# BATT_DISP.net
KiCad netlist of a schematic drawn in EAGLE
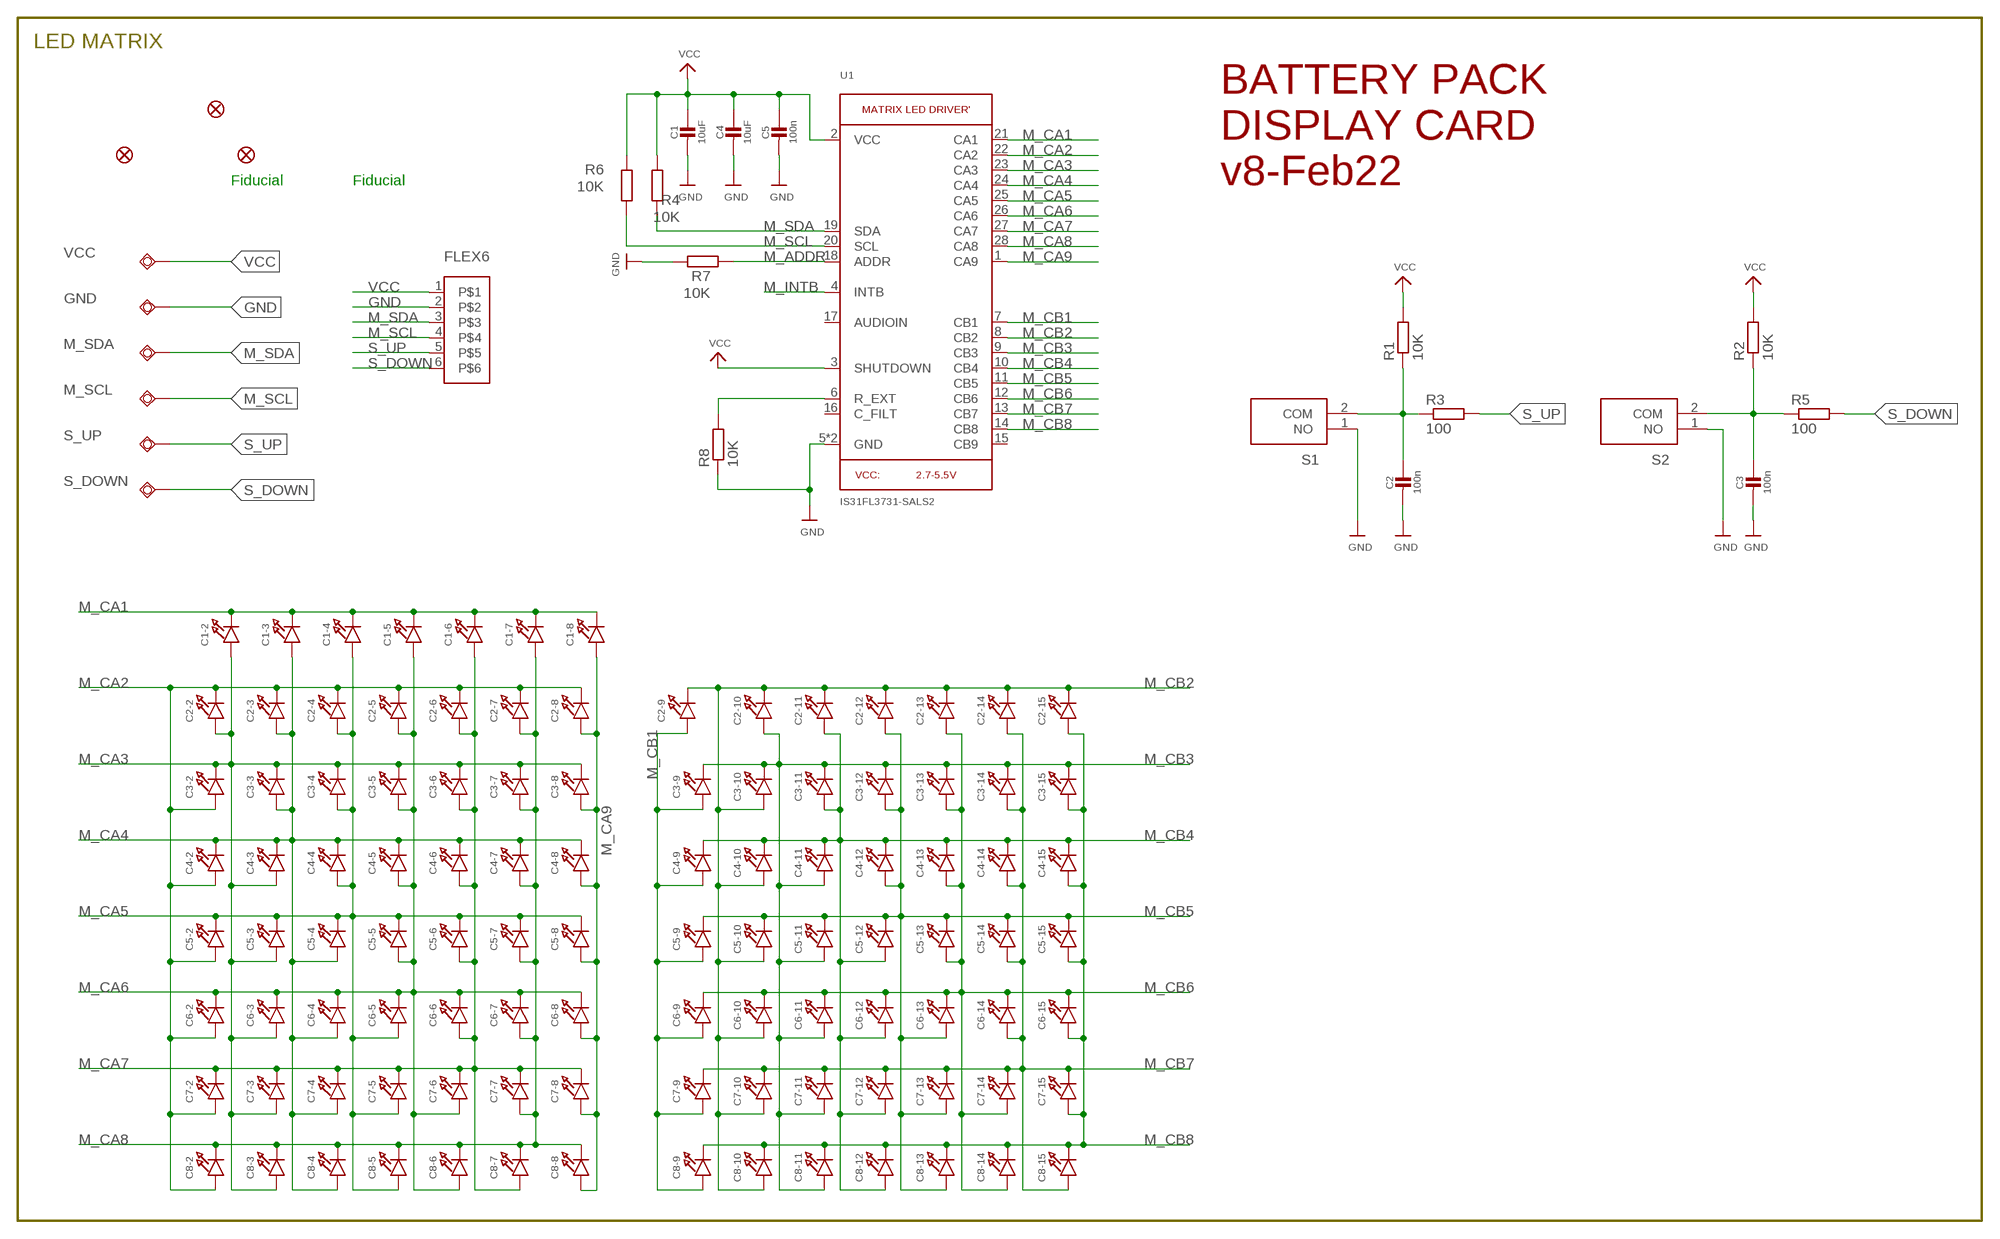
[diagram p0: schematic, sheet 1]

(export (version "E")
  (design (tool "Eeschema 10.0.6"))
  (components
    (comp (ref "C1")
      (value "10uF")
      (footprint "eagle-import:0805-NO")
      (libsource (lib "eagle-import") (part "CAP_CERAMIC0805-NOOUTLINE"))
    )
    (comp (ref "C1-2")
      (value "LED0402_NOOUTLINE")
      (footprint "eagle-import:CHIPLED_0402_NOOUTLINE")
      (libsource (lib "eagle-import") (part "LED0402_NOOUTLINE"))
    )
    (comp (ref "C1-3")
      (value "LED0402_NOOUTLINE")
      (footprint "eagle-import:CHIPLED_0402_NOOUTLINE")
      (libsource (lib "eagle-import") (part "LED0402_NOOUTLINE"))
    )
    (comp (ref "C1-4")
      (value "LED0402_NOOUTLINE")
      (footprint "eagle-import:CHIPLED_0402_NOOUTLINE")
      (libsource (lib "eagle-import") (part "LED0402_NOOUTLINE"))
    )
    (comp (ref "C1-5")
      (value "LED0402_NOOUTLINE")
      (footprint "eagle-import:CHIPLED_0402_NOOUTLINE")
      (libsource (lib "eagle-import") (part "LED0402_NOOUTLINE"))
    )
    (comp (ref "C1-6")
      (value "LED0402_NOOUTLINE")
      (footprint "eagle-import:CHIPLED_0402_NOOUTLINE")
      (libsource (lib "eagle-import") (part "LED0402_NOOUTLINE"))
    )
    (comp (ref "C1-7")
      (value "LED0402_NOOUTLINE")
      (footprint "eagle-import:CHIPLED_0402_NOOUTLINE")
      (libsource (lib "eagle-import") (part "LED0402_NOOUTLINE"))
    )
    (comp (ref "C1-8")
      (value "LED0402_NOOUTLINE")
      (footprint "eagle-import:CHIPLED_0402_NOOUTLINE")
      (libsource (lib "eagle-import") (part "LED0402_NOOUTLINE"))
    )
    (comp (ref "C2")
      (value "100n")
      (footprint "eagle-import:0805-NO")
      (libsource (lib "eagle-import") (part "CAP_CERAMIC0805-NOOUTLINE"))
    )
    (comp (ref "C2-2")
      (value "LED0402_NOOUTLINE")
      (footprint "eagle-import:CHIPLED_0402_NOOUTLINE")
      (libsource (lib "eagle-import") (part "LED0402_NOOUTLINE"))
    )
    (comp (ref "C2-3")
      (value "LED0402_NOOUTLINE")
      (footprint "eagle-import:CHIPLED_0402_NOOUTLINE")
      (libsource (lib "eagle-import") (part "LED0402_NOOUTLINE"))
    )
    (comp (ref "C2-4")
      (value "LED0402_NOOUTLINE")
      (footprint "eagle-import:CHIPLED_0402_NOOUTLINE")
      (libsource (lib "eagle-import") (part "LED0402_NOOUTLINE"))
    )
    (comp (ref "C2-5")
      (value "LED0402_NOOUTLINE")
      (footprint "eagle-import:CHIPLED_0402_NOOUTLINE")
      (libsource (lib "eagle-import") (part "LED0402_NOOUTLINE"))
    )
    (comp (ref "C2-6")
      (value "LED0402_NOOUTLINE")
      (footprint "eagle-import:CHIPLED_0402_NOOUTLINE")
      (libsource (lib "eagle-import") (part "LED0402_NOOUTLINE"))
    )
    (comp (ref "C2-7")
      (value "LED0402_NOOUTLINE")
      (footprint "eagle-import:CHIPLED_0402_NOOUTLINE")
      (libsource (lib "eagle-import") (part "LED0402_NOOUTLINE"))
    )
    (comp (ref "C2-8")
      (value "LED0402_NOOUTLINE")
      (footprint "eagle-import:CHIPLED_0402_NOOUTLINE")
      (libsource (lib "eagle-import") (part "LED0402_NOOUTLINE"))
    )
    (comp (ref "C2-9")
      (value "LED0402_NOOUTLINE")
      (footprint "eagle-import:CHIPLED_0402_NOOUTLINE")
      (libsource (lib "eagle-import") (part "LED0402_NOOUTLINE"))
    )
    (comp (ref "C2-10")
      (value "LED0402_NOOUTLINE")
      (footprint "eagle-import:CHIPLED_0402_NOOUTLINE")
      (libsource (lib "eagle-import") (part "LED0402_NOOUTLINE"))
    )
    (comp (ref "C2-11")
      (value "LED0402_NOOUTLINE")
      (footprint "eagle-import:CHIPLED_0402_NOOUTLINE")
      (libsource (lib "eagle-import") (part "LED0402_NOOUTLINE"))
    )
    (comp (ref "C2-12")
      (value "LED0402_NOOUTLINE")
      (footprint "eagle-import:CHIPLED_0402_NOOUTLINE")
      (libsource (lib "eagle-import") (part "LED0402_NOOUTLINE"))
    )
    (comp (ref "C2-13")
      (value "LED0402_NOOUTLINE")
      (footprint "eagle-import:CHIPLED_0402_NOOUTLINE")
      (libsource (lib "eagle-import") (part "LED0402_NOOUTLINE"))
    )
    (comp (ref "C2-14")
      (value "LED0402_NOOUTLINE")
      (footprint "eagle-import:CHIPLED_0402_NOOUTLINE")
      (libsource (lib "eagle-import") (part "LED0402_NOOUTLINE"))
    )
    (comp (ref "C2-15")
      (value "LED0402_NOOUTLINE")
      (footprint "eagle-import:CHIPLED_0402_NOOUTLINE")
      (libsource (lib "eagle-import") (part "LED0402_NOOUTLINE"))
    )
    (comp (ref "C3")
      (value "100n")
      (footprint "eagle-import:0805-NO")
      (libsource (lib "eagle-import") (part "CAP_CERAMIC0805-NOOUTLINE"))
    )
    (comp (ref "C3-2")
      (value "LED0402_NOOUTLINE")
      (footprint "eagle-import:CHIPLED_0402_NOOUTLINE")
      (libsource (lib "eagle-import") (part "LED0402_NOOUTLINE"))
    )
    (comp (ref "C3-3")
      (value "LED0402_NOOUTLINE")
      (footprint "eagle-import:CHIPLED_0402_NOOUTLINE")
      (libsource (lib "eagle-import") (part "LED0402_NOOUTLINE"))
    )
    (comp (ref "C3-4")
      (value "LED0402_NOOUTLINE")
      (footprint "eagle-import:CHIPLED_0402_NOOUTLINE")
      (libsource (lib "eagle-import") (part "LED0402_NOOUTLINE"))
    )
    (comp (ref "C3-5")
      (value "LED0402_NOOUTLINE")
      (footprint "eagle-import:CHIPLED_0402_NOOUTLINE")
      (libsource (lib "eagle-import") (part "LED0402_NOOUTLINE"))
    )
    (comp (ref "C3-6")
      (value "LED0402_NOOUTLINE")
      (footprint "eagle-import:CHIPLED_0402_NOOUTLINE")
      (libsource (lib "eagle-import") (part "LED0402_NOOUTLINE"))
    )
    (comp (ref "C3-7")
      (value "LED0402_NOOUTLINE")
      (footprint "eagle-import:CHIPLED_0402_NOOUTLINE")
      (libsource (lib "eagle-import") (part "LED0402_NOOUTLINE"))
    )
    (comp (ref "C3-8")
      (value "LED0402_NOOUTLINE")
      (footprint "eagle-import:CHIPLED_0402_NOOUTLINE")
      (libsource (lib "eagle-import") (part "LED0402_NOOUTLINE"))
    )
    (comp (ref "C3-9")
      (value "LED0402_NOOUTLINE")
      (footprint "eagle-import:CHIPLED_0402_NOOUTLINE")
      (libsource (lib "eagle-import") (part "LED0402_NOOUTLINE"))
    )
    (comp (ref "C3-10")
      (value "LED0402_NOOUTLINE")
      (footprint "eagle-import:CHIPLED_0402_NOOUTLINE")
      (libsource (lib "eagle-import") (part "LED0402_NOOUTLINE"))
    )
    (comp (ref "C3-11")
      (value "LED0402_NOOUTLINE")
      (footprint "eagle-import:CHIPLED_0402_NOOUTLINE")
      (libsource (lib "eagle-import") (part "LED0402_NOOUTLINE"))
    )
    (comp (ref "C3-12")
      (value "LED0402_NOOUTLINE")
      (footprint "eagle-import:CHIPLED_0402_NOOUTLINE")
      (libsource (lib "eagle-import") (part "LED0402_NOOUTLINE"))
    )
    (comp (ref "C3-13")
      (value "LED0402_NOOUTLINE")
      (footprint "eagle-import:CHIPLED_0402_NOOUTLINE")
      (libsource (lib "eagle-import") (part "LED0402_NOOUTLINE"))
    )
    (comp (ref "C3-14")
      (value "LED0402_NOOUTLINE")
      (footprint "eagle-import:CHIPLED_0402_NOOUTLINE")
      (libsource (lib "eagle-import") (part "LED0402_NOOUTLINE"))
    )
    (comp (ref "C3-15")
      (value "LED0402_NOOUTLINE")
      (footprint "eagle-import:CHIPLED_0402_NOOUTLINE")
      (libsource (lib "eagle-import") (part "LED0402_NOOUTLINE"))
    )
    (comp (ref "C4")
      (value "10uF")
      (footprint "eagle-import:0805-NO")
      (libsource (lib "eagle-import") (part "CAP_CERAMIC0805-NOOUTLINE"))
    )
    (comp (ref "C4-2")
      (value "LED0402_NOOUTLINE")
      (footprint "eagle-import:CHIPLED_0402_NOOUTLINE")
      (libsource (lib "eagle-import") (part "LED0402_NOOUTLINE"))
    )
    (comp (ref "C4-3")
      (value "LED0402_NOOUTLINE")
      (footprint "eagle-import:CHIPLED_0402_NOOUTLINE")
      (libsource (lib "eagle-import") (part "LED0402_NOOUTLINE"))
    )
    (comp (ref "C4-4")
      (value "LED0402_NOOUTLINE")
      (footprint "eagle-import:CHIPLED_0402_NOOUTLINE")
      (libsource (lib "eagle-import") (part "LED0402_NOOUTLINE"))
    )
    (comp (ref "C4-5")
      (value "LED0402_NOOUTLINE")
      (footprint "eagle-import:CHIPLED_0402_NOOUTLINE")
      (libsource (lib "eagle-import") (part "LED0402_NOOUTLINE"))
    )
    (comp (ref "C4-6")
      (value "LED0402_NOOUTLINE")
      (footprint "eagle-import:CHIPLED_0402_NOOUTLINE")
      (libsource (lib "eagle-import") (part "LED0402_NOOUTLINE"))
    )
    (comp (ref "C4-7")
      (value "LED0402_NOOUTLINE")
      (footprint "eagle-import:CHIPLED_0402_NOOUTLINE")
      (libsource (lib "eagle-import") (part "LED0402_NOOUTLINE"))
    )
    (comp (ref "C4-8")
      (value "LED0402_NOOUTLINE")
      (footprint "eagle-import:CHIPLED_0402_NOOUTLINE")
      (libsource (lib "eagle-import") (part "LED0402_NOOUTLINE"))
    )
    (comp (ref "C4-9")
      (value "LED0402_NOOUTLINE")
      (footprint "eagle-import:CHIPLED_0402_NOOUTLINE")
      (libsource (lib "eagle-import") (part "LED0402_NOOUTLINE"))
    )
    (comp (ref "C4-10")
      (value "LED0402_NOOUTLINE")
      (footprint "eagle-import:CHIPLED_0402_NOOUTLINE")
      (libsource (lib "eagle-import") (part "LED0402_NOOUTLINE"))
    )
    (comp (ref "C4-11")
      (value "LED0402_NOOUTLINE")
      (footprint "eagle-import:CHIPLED_0402_NOOUTLINE")
      (libsource (lib "eagle-import") (part "LED0402_NOOUTLINE"))
    )
    (comp (ref "C4-12")
      (value "LED0402_NOOUTLINE")
      (footprint "eagle-import:CHIPLED_0402_NOOUTLINE")
      (libsource (lib "eagle-import") (part "LED0402_NOOUTLINE"))
    )
    (comp (ref "C4-13")
      (value "LED0402_NOOUTLINE")
      (footprint "eagle-import:CHIPLED_0402_NOOUTLINE")
      (libsource (lib "eagle-import") (part "LED0402_NOOUTLINE"))
    )
    (comp (ref "C4-14")
      (value "LED0402_NOOUTLINE")
      (footprint "eagle-import:CHIPLED_0402_NOOUTLINE")
      (libsource (lib "eagle-import") (part "LED0402_NOOUTLINE"))
    )
    (comp (ref "C4-15")
      (value "LED0402_NOOUTLINE")
      (footprint "eagle-import:CHIPLED_0402_NOOUTLINE")
      (libsource (lib "eagle-import") (part "LED0402_NOOUTLINE"))
    )
    (comp (ref "C5")
      (value "100n")
      (footprint "eagle-import:0805-NO")
      (libsource (lib "eagle-import") (part "CAP_CERAMIC0805-NOOUTLINE"))
    )
    (comp (ref "C5-2")
      (value "LED0402_NOOUTLINE")
      (footprint "eagle-import:CHIPLED_0402_NOOUTLINE")
      (libsource (lib "eagle-import") (part "LED0402_NOOUTLINE"))
    )
    (comp (ref "C5-3")
      (value "LED0402_NOOUTLINE")
      (footprint "eagle-import:CHIPLED_0402_NOOUTLINE")
      (libsource (lib "eagle-import") (part "LED0402_NOOUTLINE"))
    )
    (comp (ref "C5-4")
      (value "LED0402_NOOUTLINE")
      (footprint "eagle-import:CHIPLED_0402_NOOUTLINE")
      (libsource (lib "eagle-import") (part "LED0402_NOOUTLINE"))
    )
    (comp (ref "C5-5")
      (value "LED0402_NOOUTLINE")
      (footprint "eagle-import:CHIPLED_0402_NOOUTLINE")
      (libsource (lib "eagle-import") (part "LED0402_NOOUTLINE"))
    )
    (comp (ref "C5-6")
      (value "LED0402_NOOUTLINE")
      (footprint "eagle-import:CHIPLED_0402_NOOUTLINE")
      (libsource (lib "eagle-import") (part "LED0402_NOOUTLINE"))
    )
    (comp (ref "C5-7")
      (value "LED0402_NOOUTLINE")
      (footprint "eagle-import:CHIPLED_0402_NOOUTLINE")
      (libsource (lib "eagle-import") (part "LED0402_NOOUTLINE"))
    )
    (comp (ref "C5-8")
      (value "LED0402_NOOUTLINE")
      (footprint "eagle-import:CHIPLED_0402_NOOUTLINE")
      (libsource (lib "eagle-import") (part "LED0402_NOOUTLINE"))
    )
    (comp (ref "C5-9")
      (value "LED0402_NOOUTLINE")
      (footprint "eagle-import:CHIPLED_0402_NOOUTLINE")
      (libsource (lib "eagle-import") (part "LED0402_NOOUTLINE"))
    )
    (comp (ref "C5-10")
      (value "LED0402_NOOUTLINE")
      (footprint "eagle-import:CHIPLED_0402_NOOUTLINE")
      (libsource (lib "eagle-import") (part "LED0402_NOOUTLINE"))
    )
    (comp (ref "C5-11")
      (value "LED0402_NOOUTLINE")
      (footprint "eagle-import:CHIPLED_0402_NOOUTLINE")
      (libsource (lib "eagle-import") (part "LED0402_NOOUTLINE"))
    )
    (comp (ref "C5-12")
      (value "LED0402_NOOUTLINE")
      (footprint "eagle-import:CHIPLED_0402_NOOUTLINE")
      (libsource (lib "eagle-import") (part "LED0402_NOOUTLINE"))
    )
    (comp (ref "C5-13")
      (value "LED0402_NOOUTLINE")
      (footprint "eagle-import:CHIPLED_0402_NOOUTLINE")
      (libsource (lib "eagle-import") (part "LED0402_NOOUTLINE"))
    )
    (comp (ref "C5-14")
      (value "LED0402_NOOUTLINE")
      (footprint "eagle-import:CHIPLED_0402_NOOUTLINE")
      (libsource (lib "eagle-import") (part "LED0402_NOOUTLINE"))
    )
    (comp (ref "C5-15")
      (value "LED0402_NOOUTLINE")
      (footprint "eagle-import:CHIPLED_0402_NOOUTLINE")
      (libsource (lib "eagle-import") (part "LED0402_NOOUTLINE"))
    )
    (comp (ref "C6-2")
      (value "LED0402_NOOUTLINE")
      (footprint "eagle-import:CHIPLED_0402_NOOUTLINE")
      (libsource (lib "eagle-import") (part "LED0402_NOOUTLINE"))
    )
    (comp (ref "C6-3")
      (value "LED0402_NOOUTLINE")
      (footprint "eagle-import:CHIPLED_0402_NOOUTLINE")
      (libsource (lib "eagle-import") (part "LED0402_NOOUTLINE"))
    )
    (comp (ref "C6-4")
      (value "LED0402_NOOUTLINE")
      (footprint "eagle-import:CHIPLED_0402_NOOUTLINE")
      (libsource (lib "eagle-import") (part "LED0402_NOOUTLINE"))
    )
    (comp (ref "C6-5")
      (value "LED0402_NOOUTLINE")
      (footprint "eagle-import:CHIPLED_0402_NOOUTLINE")
      (libsource (lib "eagle-import") (part "LED0402_NOOUTLINE"))
    )
    (comp (ref "C6-6")
      (value "LED0402_NOOUTLINE")
      (footprint "eagle-import:CHIPLED_0402_NOOUTLINE")
      (libsource (lib "eagle-import") (part "LED0402_NOOUTLINE"))
    )
    (comp (ref "C6-7")
      (value "LED0402_NOOUTLINE")
      (footprint "eagle-import:CHIPLED_0402_NOOUTLINE")
      (libsource (lib "eagle-import") (part "LED0402_NOOUTLINE"))
    )
    (comp (ref "C6-8")
      (value "LED0402_NOOUTLINE")
      (footprint "eagle-import:CHIPLED_0402_NOOUTLINE")
      (libsource (lib "eagle-import") (part "LED0402_NOOUTLINE"))
    )
    (comp (ref "C6-9")
      (value "LED0402_NOOUTLINE")
      (footprint "eagle-import:CHIPLED_0402_NOOUTLINE")
      (libsource (lib "eagle-import") (part "LED0402_NOOUTLINE"))
    )
    (comp (ref "C6-10")
      (value "LED0402_NOOUTLINE")
      (footprint "eagle-import:CHIPLED_0402_NOOUTLINE")
      (libsource (lib "eagle-import") (part "LED0402_NOOUTLINE"))
    )
    (comp (ref "C6-11")
      (value "LED0402_NOOUTLINE")
      (footprint "eagle-import:CHIPLED_0402_NOOUTLINE")
      (libsource (lib "eagle-import") (part "LED0402_NOOUTLINE"))
    )
    (comp (ref "C6-12")
      (value "LED0402_NOOUTLINE")
      (footprint "eagle-import:CHIPLED_0402_NOOUTLINE")
      (libsource (lib "eagle-import") (part "LED0402_NOOUTLINE"))
    )
    (comp (ref "C6-13")
      (value "LED0402_NOOUTLINE")
      (footprint "eagle-import:CHIPLED_0402_NOOUTLINE")
      (libsource (lib "eagle-import") (part "LED0402_NOOUTLINE"))
    )
    (comp (ref "C6-14")
      (value "LED0402_NOOUTLINE")
      (footprint "eagle-import:CHIPLED_0402_NOOUTLINE")
      (libsource (lib "eagle-import") (part "LED0402_NOOUTLINE"))
    )
    (comp (ref "C6-15")
      (value "LED0402_NOOUTLINE")
      (footprint "eagle-import:CHIPLED_0402_NOOUTLINE")
      (libsource (lib "eagle-import") (part "LED0402_NOOUTLINE"))
    )
    (comp (ref "C7-2")
      (value "LED0402_NOOUTLINE")
      (footprint "eagle-import:CHIPLED_0402_NOOUTLINE")
      (libsource (lib "eagle-import") (part "LED0402_NOOUTLINE"))
    )
    (comp (ref "C7-3")
      (value "LED0402_NOOUTLINE")
      (footprint "eagle-import:CHIPLED_0402_NOOUTLINE")
      (libsource (lib "eagle-import") (part "LED0402_NOOUTLINE"))
    )
    (comp (ref "C7-4")
      (value "LED0402_NOOUTLINE")
      (footprint "eagle-import:CHIPLED_0402_NOOUTLINE")
      (libsource (lib "eagle-import") (part "LED0402_NOOUTLINE"))
    )
    (comp (ref "C7-5")
      (value "LED0402_NOOUTLINE")
      (footprint "eagle-import:CHIPLED_0402_NOOUTLINE")
      (libsource (lib "eagle-import") (part "LED0402_NOOUTLINE"))
    )
    (comp (ref "C7-6")
      (value "LED0402_NOOUTLINE")
      (footprint "eagle-import:CHIPLED_0402_NOOUTLINE")
      (libsource (lib "eagle-import") (part "LED0402_NOOUTLINE"))
    )
    (comp (ref "C7-7")
      (value "LED0402_NOOUTLINE")
      (footprint "eagle-import:CHIPLED_0402_NOOUTLINE")
      (libsource (lib "eagle-import") (part "LED0402_NOOUTLINE"))
    )
    (comp (ref "C7-8")
      (value "LED0402_NOOUTLINE")
      (footprint "eagle-import:CHIPLED_0402_NOOUTLINE")
      (libsource (lib "eagle-import") (part "LED0402_NOOUTLINE"))
    )
    (comp (ref "C7-9")
      (value "LED0402_NOOUTLINE")
      (footprint "eagle-import:CHIPLED_0402_NOOUTLINE")
      (libsource (lib "eagle-import") (part "LED0402_NOOUTLINE"))
    )
    (comp (ref "C7-10")
      (value "LED0402_NOOUTLINE")
      (footprint "eagle-import:CHIPLED_0402_NOOUTLINE")
      (libsource (lib "eagle-import") (part "LED0402_NOOUTLINE"))
    )
    (comp (ref "C7-11")
      (value "LED0402_NOOUTLINE")
      (footprint "eagle-import:CHIPLED_0402_NOOUTLINE")
      (libsource (lib "eagle-import") (part "LED0402_NOOUTLINE"))
    )
    (comp (ref "C7-12")
      (value "LED0402_NOOUTLINE")
      (footprint "eagle-import:CHIPLED_0402_NOOUTLINE")
      (libsource (lib "eagle-import") (part "LED0402_NOOUTLINE"))
    )
    (comp (ref "C7-13")
      (value "LED0402_NOOUTLINE")
      (footprint "eagle-import:CHIPLED_0402_NOOUTLINE")
      (libsource (lib "eagle-import") (part "LED0402_NOOUTLINE"))
    )
    (comp (ref "C7-14")
      (value "LED0402_NOOUTLINE")
      (footprint "eagle-import:CHIPLED_0402_NOOUTLINE")
      (libsource (lib "eagle-import") (part "LED0402_NOOUTLINE"))
    )
    (comp (ref "C7-15")
      (value "LED0402_NOOUTLINE")
      (footprint "eagle-import:CHIPLED_0402_NOOUTLINE")
      (libsource (lib "eagle-import") (part "LED0402_NOOUTLINE"))
    )
    (comp (ref "C8-2")
      (value "LED0402_NOOUTLINE")
      (footprint "eagle-import:CHIPLED_0402_NOOUTLINE")
      (libsource (lib "eagle-import") (part "LED0402_NOOUTLINE"))
    )
    (comp (ref "C8-3")
      (value "LED0402_NOOUTLINE")
      (footprint "eagle-import:CHIPLED_0402_NOOUTLINE")
      (libsource (lib "eagle-import") (part "LED0402_NOOUTLINE"))
    )
    (comp (ref "C8-4")
      (value "LED0402_NOOUTLINE")
      (footprint "eagle-import:CHIPLED_0402_NOOUTLINE")
      (libsource (lib "eagle-import") (part "LED0402_NOOUTLINE"))
    )
    (comp (ref "C8-5")
      (value "LED0402_NOOUTLINE")
      (footprint "eagle-import:CHIPLED_0402_NOOUTLINE")
      (libsource (lib "eagle-import") (part "LED0402_NOOUTLINE"))
    )
    (comp (ref "C8-6")
      (value "LED0402_NOOUTLINE")
      (footprint "eagle-import:CHIPLED_0402_NOOUTLINE")
      (libsource (lib "eagle-import") (part "LED0402_NOOUTLINE"))
    )
    (comp (ref "C8-7")
      (value "LED0402_NOOUTLINE")
      (footprint "eagle-import:CHIPLED_0402_NOOUTLINE")
      (libsource (lib "eagle-import") (part "LED0402_NOOUTLINE"))
    )
    (comp (ref "C8-8")
      (value "LED0402_NOOUTLINE")
      (footprint "eagle-import:CHIPLED_0402_NOOUTLINE")
      (libsource (lib "eagle-import") (part "LED0402_NOOUTLINE"))
    )
    (comp (ref "C8-9")
      (value "LED0402_NOOUTLINE")
      (footprint "eagle-import:CHIPLED_0402_NOOUTLINE")
      (libsource (lib "eagle-import") (part "LED0402_NOOUTLINE"))
    )
    (comp (ref "C8-10")
      (value "LED0402_NOOUTLINE")
      (footprint "eagle-import:CHIPLED_0402_NOOUTLINE")
      (libsource (lib "eagle-import") (part "LED0402_NOOUTLINE"))
    )
    (comp (ref "C8-11")
      (value "LED0402_NOOUTLINE")
      (footprint "eagle-import:CHIPLED_0402_NOOUTLINE")
      (libsource (lib "eagle-import") (part "LED0402_NOOUTLINE"))
    )
    (comp (ref "C8-12")
      (value "LED0402_NOOUTLINE")
      (footprint "eagle-import:CHIPLED_0402_NOOUTLINE")
      (libsource (lib "eagle-import") (part "LED0402_NOOUTLINE"))
    )
    (comp (ref "C8-13")
      (value "LED0402_NOOUTLINE")
      (footprint "eagle-import:CHIPLED_0402_NOOUTLINE")
      (libsource (lib "eagle-import") (part "LED0402_NOOUTLINE"))
    )
    (comp (ref "C8-14")
      (value "LED0402_NOOUTLINE")
      (footprint "eagle-import:CHIPLED_0402_NOOUTLINE")
      (libsource (lib "eagle-import") (part "LED0402_NOOUTLINE"))
    )
    (comp (ref "C8-15")
      (value "LED0402_NOOUTLINE")
      (footprint "eagle-import:CHIPLED_0402_NOOUTLINE")
      (libsource (lib "eagle-import") (part "LED0402_NOOUTLINE"))
    )
    (comp (ref "FD1")
      (value "FIDUCIALUFIDUCIAL")
      (footprint "eagle-import:FIDUCIAL-MICRO")
      (libsource (lib "eagle-import") (part "FIDUCIALUFIDUCIAL"))
    )
    (comp (ref "FD2")
      (value "FIDUCIAL\"\"")
      (footprint "eagle-import:FIDUCIAL_1MM")
      (libsource (lib "eagle-import") (part "FIDUCIAL{dblquote}{dblquote}"))
    )
    (comp (ref "FD3")
      (value "FIDUCIAL\"\"")
      (footprint "eagle-import:FIDUCIAL_1MM")
      (libsource (lib "eagle-import") (part "FIDUCIAL{dblquote}{dblquote}"))
    )
    (comp (ref "GND")
      (value "TESTPAD_TPSQB1,27")
      (footprint "eagle-import:TESTPAD_B1,27")
      (libsource (lib "eagle-import") (part "TESTPAD_TPSQB1,27"))
    )
    (comp (ref "K1")
      (value "FLEX6")
      (footprint "eagle-import:FLEX6")
      (libsource (lib "eagle-import") (part "FLEX6"))
    )
    (comp (ref "M_SCL")
      (value "TESTPAD_TPSQB1,27")
      (footprint "eagle-import:TESTPAD_B1,27")
      (libsource (lib "eagle-import") (part "TESTPAD_TPSQB1,27"))
    )
    (comp (ref "M_SDA")
      (value "TESTPAD_TPSQB1,27")
      (footprint "eagle-import:TESTPAD_B1,27")
      (libsource (lib "eagle-import") (part "TESTPAD_TPSQB1,27"))
    )
    (comp (ref "R1")
      (value "10K")
      (footprint "eagle-import:R0603")
      (libsource (lib "eagle-import") (part "R-EU_R0603"))
    )
    (comp (ref "R2")
      (value "10K")
      (footprint "eagle-import:R0603")
      (libsource (lib "eagle-import") (part "R-EU_R0603"))
    )
    (comp (ref "R3")
      (value "100")
      (footprint "eagle-import:R0603")
      (libsource (lib "eagle-import") (part "R-EU_R0603"))
    )
    (comp (ref "R4")
      (value "10K")
      (footprint "eagle-import:R0603")
      (libsource (lib "eagle-import") (part "R-EU_R0603"))
    )
    (comp (ref "R5")
      (value "100")
      (footprint "eagle-import:R0603")
      (libsource (lib "eagle-import") (part "R-EU_R0603"))
    )
    (comp (ref "R6")
      (value "10K")
      (footprint "eagle-import:R0603")
      (libsource (lib "eagle-import") (part "R-EU_R0603"))
    )
    (comp (ref "R7")
      (value "10K")
      (footprint "eagle-import:R0603")
      (libsource (lib "eagle-import") (part "R-EU_R0603"))
    )
    (comp (ref "R8")
      (value "10K")
      (footprint "eagle-import:R0603")
      (libsource (lib "eagle-import") (part "R-EU_R0603"))
    )
    (comp (ref "S1")
      (value "KXT311LHS")
      (footprint "eagle-import:KXT311LHS")
      (fields (field (name "MOUSER_PART_NUMBER") "611-KXT311LHS"))
      (libsource (lib "eagle-import") (part "KXT311LHS"))
    )
    (comp (ref "S2")
      (value "KXT311LHS")
      (footprint "eagle-import:KXT311LHS")
      (fields (field (name "MOUSER_PART_NUMBER") "611-KXT311LHS"))
      (libsource (lib "eagle-import") (part "KXT311LHS"))
    )
    (comp (ref "S_DOWN")
      (value "TESTPAD_TPSQB1,27")
      (footprint "eagle-import:TESTPAD_B1,27")
      (libsource (lib "eagle-import") (part "TESTPAD_TPSQB1,27"))
    )
    (comp (ref "S_UP")
      (value "TESTPAD_TPSQB1,27")
      (footprint "eagle-import:TESTPAD_B1,27")
      (libsource (lib "eagle-import") (part "TESTPAD_TPSQB1,27"))
    )
    (comp (ref "U1")
      (value "IS31FL3731-SALS2")
      (footprint "eagle-import:QFN28_4MM_0.4MM")
      (libsource (lib "eagle-import") (part "IS31FL3731QFN"))
    )
    (comp (ref "VCC")
      (value "TESTPAD_TPSQB1,27")
      (footprint "eagle-import:TESTPAD_B1,27")
      (libsource (lib "eagle-import") (part "TESTPAD_TPSQB1,27"))
    )
  )
  (nets
    (net (code "1") (name "/M_ADDR") (class "Default")
      (node (ref "R7") (pin "1") (pinfunction "1_1") (pintype "passive"))
      (node (ref "U1") (pin "18") (pinfunction "ADDR_18") (pintype "bidirectional"))
    )
    (net (code "2") (name "/M_CA1") (class "Default")
      (node (ref "C1-2") (pin "C") (pinfunction "C_C") (pintype "passive"))
      (node (ref "C1-3") (pin "C") (pinfunction "C_C") (pintype "passive"))
      (node (ref "C1-4") (pin "C") (pinfunction "C_C") (pintype "passive"))
      (node (ref "C1-5") (pin "C") (pinfunction "C_C") (pintype "passive"))
      (node (ref "C1-6") (pin "C") (pinfunction "C_C") (pintype "passive"))
      (node (ref "C1-7") (pin "C") (pinfunction "C_C") (pintype "passive"))
      (node (ref "C1-8") (pin "C") (pinfunction "C_C") (pintype "passive"))
      (node (ref "U1") (pin "21") (pinfunction "CA1_21") (pintype "bidirectional"))
    )
    (net (code "3") (name "/M_CA2") (class "Default")
      (node (ref "C2-2") (pin "C") (pinfunction "C_C") (pintype "passive"))
      (node (ref "C2-3") (pin "C") (pinfunction "C_C") (pintype "passive"))
      (node (ref "C2-4") (pin "C") (pinfunction "C_C") (pintype "passive"))
      (node (ref "C2-5") (pin "C") (pinfunction "C_C") (pintype "passive"))
      (node (ref "C2-6") (pin "C") (pinfunction "C_C") (pintype "passive"))
      (node (ref "C2-7") (pin "C") (pinfunction "C_C") (pintype "passive"))
      (node (ref "C2-8") (pin "C") (pinfunction "C_C") (pintype "passive"))
      (node (ref "C3-2") (pin "A") (pinfunction "A_A") (pintype "passive"))
      (node (ref "C4-2") (pin "A") (pinfunction "A_A") (pintype "passive"))
      (node (ref "C5-2") (pin "A") (pinfunction "A_A") (pintype "passive"))
      (node (ref "C6-2") (pin "A") (pinfunction "A_A") (pintype "passive"))
      (node (ref "C7-2") (pin "A") (pinfunction "A_A") (pintype "passive"))
      (node (ref "C8-2") (pin "A") (pinfunction "A_A") (pintype "passive"))
      (node (ref "U1") (pin "22") (pinfunction "CA2_22") (pintype "bidirectional"))
    )
    (net (code "4") (name "/M_CA3") (class "Default")
      (node (ref "C1-2") (pin "A") (pinfunction "A_A") (pintype "passive"))
      (node (ref "C2-2") (pin "A") (pinfunction "A_A") (pintype "passive"))
      (node (ref "C3-2") (pin "C") (pinfunction "C_C") (pintype "passive"))
      (node (ref "C3-3") (pin "C") (pinfunction "C_C") (pintype "passive"))
      (node (ref "C3-4") (pin "C") (pinfunction "C_C") (pintype "passive"))
      (node (ref "C3-5") (pin "C") (pinfunction "C_C") (pintype "passive"))
      (node (ref "C3-6") (pin "C") (pinfunction "C_C") (pintype "passive"))
      (node (ref "C3-7") (pin "C") (pinfunction "C_C") (pintype "passive"))
      (node (ref "C3-8") (pin "C") (pinfunction "C_C") (pintype "passive"))
      (node (ref "C4-3") (pin "A") (pinfunction "A_A") (pintype "passive"))
      (node (ref "C5-3") (pin "A") (pinfunction "A_A") (pintype "passive"))
      (node (ref "C6-3") (pin "A") (pinfunction "A_A") (pintype "passive"))
      (node (ref "C7-3") (pin "A") (pinfunction "A_A") (pintype "passive"))
      (node (ref "C8-3") (pin "A") (pinfunction "A_A") (pintype "passive"))
      (node (ref "U1") (pin "23") (pinfunction "CA3_23") (pintype "bidirectional"))
    )
    (net (code "5") (name "/M_CA4") (class "Default")
      (node (ref "C1-3") (pin "A") (pinfunction "A_A") (pintype "passive"))
      (node (ref "C2-3") (pin "A") (pinfunction "A_A") (pintype "passive"))
      (node (ref "C3-3") (pin "A") (pinfunction "A_A") (pintype "passive"))
      (node (ref "C4-2") (pin "C") (pinfunction "C_C") (pintype "passive"))
      (node (ref "C4-3") (pin "C") (pinfunction "C_C") (pintype "passive"))
      (node (ref "C4-4") (pin "C") (pinfunction "C_C") (pintype "passive"))
      (node (ref "C4-5") (pin "C") (pinfunction "C_C") (pintype "passive"))
      (node (ref "C4-6") (pin "C") (pinfunction "C_C") (pintype "passive"))
      (node (ref "C4-7") (pin "C") (pinfunction "C_C") (pintype "passive"))
      (node (ref "C4-8") (pin "C") (pinfunction "C_C") (pintype "passive"))
      (node (ref "C5-4") (pin "A") (pinfunction "A_A") (pintype "passive"))
      (node (ref "C6-4") (pin "A") (pinfunction "A_A") (pintype "passive"))
      (node (ref "C7-4") (pin "A") (pinfunction "A_A") (pintype "passive"))
      (node (ref "C8-4") (pin "A") (pinfunction "A_A") (pintype "passive"))
      (node (ref "U1") (pin "24") (pinfunction "CA4_24") (pintype "bidirectional"))
    )
    (net (code "6") (name "/M_CA5") (class "Default")
      (node (ref "C1-4") (pin "A") (pinfunction "A_A") (pintype "passive"))
      (node (ref "C2-4") (pin "A") (pinfunction "A_A") (pintype "passive"))
      (node (ref "C3-4") (pin "A") (pinfunction "A_A") (pintype "passive"))
      (node (ref "C4-4") (pin "A") (pinfunction "A_A") (pintype "passive"))
      (node (ref "C5-2") (pin "C") (pinfunction "C_C") (pintype "passive"))
      (node (ref "C5-3") (pin "C") (pinfunction "C_C") (pintype "passive"))
      (node (ref "C5-4") (pin "C") (pinfunction "C_C") (pintype "passive"))
      (node (ref "C5-5") (pin "C") (pinfunction "C_C") (pintype "passive"))
      (node (ref "C5-6") (pin "C") (pinfunction "C_C") (pintype "passive"))
      (node (ref "C5-7") (pin "C") (pinfunction "C_C") (pintype "passive"))
      (node (ref "C5-8") (pin "C") (pinfunction "C_C") (pintype "passive"))
      (node (ref "C6-5") (pin "A") (pinfunction "A_A") (pintype "passive"))
      (node (ref "C7-5") (pin "A") (pinfunction "A_A") (pintype "passive"))
      (node (ref "C8-5") (pin "A") (pinfunction "A_A") (pintype "passive"))
      (node (ref "U1") (pin "25") (pinfunction "CA5_25") (pintype "bidirectional"))
    )
    (net (code "7") (name "/M_CA6") (class "Default")
      (node (ref "C1-5") (pin "A") (pinfunction "A_A") (pintype "passive"))
      (node (ref "C2-5") (pin "A") (pinfunction "A_A") (pintype "passive"))
      (node (ref "C3-5") (pin "A") (pinfunction "A_A") (pintype "passive"))
      (node (ref "C4-5") (pin "A") (pinfunction "A_A") (pintype "passive"))
      (node (ref "C5-5") (pin "A") (pinfunction "A_A") (pintype "passive"))
      (node (ref "C6-2") (pin "C") (pinfunction "C_C") (pintype "passive"))
      (node (ref "C6-3") (pin "C") (pinfunction "C_C") (pintype "passive"))
      (node (ref "C6-4") (pin "C") (pinfunction "C_C") (pintype "passive"))
      (node (ref "C6-5") (pin "C") (pinfunction "C_C") (pintype "passive"))
      (node (ref "C6-6") (pin "C") (pinfunction "C_C") (pintype "passive"))
      (node (ref "C6-7") (pin "C") (pinfunction "C_C") (pintype "passive"))
      (node (ref "C6-8") (pin "C") (pinfunction "C_C") (pintype "passive"))
      (node (ref "C7-6") (pin "A") (pinfunction "A_A") (pintype "passive"))
      (node (ref "C8-6") (pin "A") (pinfunction "A_A") (pintype "passive"))
      (node (ref "U1") (pin "26") (pinfunction "CA6_26") (pintype "bidirectional"))
    )
    (net (code "8") (name "/M_CA7") (class "Default")
      (node (ref "C1-6") (pin "A") (pinfunction "A_A") (pintype "passive"))
      (node (ref "C2-6") (pin "A") (pinfunction "A_A") (pintype "passive"))
      (node (ref "C3-6") (pin "A") (pinfunction "A_A") (pintype "passive"))
      (node (ref "C4-6") (pin "A") (pinfunction "A_A") (pintype "passive"))
      (node (ref "C5-6") (pin "A") (pinfunction "A_A") (pintype "passive"))
      (node (ref "C6-6") (pin "A") (pinfunction "A_A") (pintype "passive"))
      (node (ref "C7-2") (pin "C") (pinfunction "C_C") (pintype "passive"))
      (node (ref "C7-3") (pin "C") (pinfunction "C_C") (pintype "passive"))
      (node (ref "C7-4") (pin "C") (pinfunction "C_C") (pintype "passive"))
      (node (ref "C7-5") (pin "C") (pinfunction "C_C") (pintype "passive"))
      (node (ref "C7-6") (pin "C") (pinfunction "C_C") (pintype "passive"))
      (node (ref "C7-7") (pin "C") (pinfunction "C_C") (pintype "passive"))
      (node (ref "C7-8") (pin "C") (pinfunction "C_C") (pintype "passive"))
      (node (ref "C8-7") (pin "A") (pinfunction "A_A") (pintype "passive"))
      (node (ref "U1") (pin "27") (pinfunction "CA7_27") (pintype "bidirectional"))
    )
    (net (code "9") (name "/M_CA8") (class "Default")
      (node (ref "C1-7") (pin "A") (pinfunction "A_A") (pintype "passive"))
      (node (ref "C2-7") (pin "A") (pinfunction "A_A") (pintype "passive"))
      (node (ref "C3-7") (pin "A") (pinfunction "A_A") (pintype "passive"))
      (node (ref "C4-7") (pin "A") (pinfunction "A_A") (pintype "passive"))
      (node (ref "C5-7") (pin "A") (pinfunction "A_A") (pintype "passive"))
      (node (ref "C6-7") (pin "A") (pinfunction "A_A") (pintype "passive"))
      (node (ref "C7-7") (pin "A") (pinfunction "A_A") (pintype "passive"))
      (node (ref "C8-2") (pin "C") (pinfunction "C_C") (pintype "passive"))
      (node (ref "C8-3") (pin "C") (pinfunction "C_C") (pintype "passive"))
      (node (ref "C8-4") (pin "C") (pinfunction "C_C") (pintype "passive"))
      (node (ref "C8-5") (pin "C") (pinfunction "C_C") (pintype "passive"))
      (node (ref "C8-6") (pin "C") (pinfunction "C_C") (pintype "passive"))
      (node (ref "C8-7") (pin "C") (pinfunction "C_C") (pintype "passive"))
      (node (ref "C8-8") (pin "C") (pinfunction "C_C") (pintype "passive"))
      (node (ref "U1") (pin "28") (pinfunction "CA8_28") (pintype "bidirectional"))
    )
    (net (code "10") (name "/M_CA9") (class "Default")
      (node (ref "C1-8") (pin "A") (pinfunction "A_A") (pintype "passive"))
      (node (ref "C2-8") (pin "A") (pinfunction "A_A") (pintype "passive"))
      (node (ref "C3-8") (pin "A") (pinfunction "A_A") (pintype "passive"))
      (node (ref "C4-8") (pin "A") (pinfunction "A_A") (pintype "passive"))
      (node (ref "C5-8") (pin "A") (pinfunction "A_A") (pintype "passive"))
      (node (ref "C6-8") (pin "A") (pinfunction "A_A") (pintype "passive"))
      (node (ref "C7-8") (pin "A") (pinfunction "A_A") (pintype "passive"))
      (node (ref "C8-8") (pin "A") (pinfunction "A_A") (pintype "passive"))
      (node (ref "U1") (pin "1") (pinfunction "CA9_1") (pintype "bidirectional"))
    )
    (net (code "11") (name "/M_CB1") (class "Default")
      (node (ref "C2-9") (pin "A") (pinfunction "A_A") (pintype "passive"))
      (node (ref "C3-9") (pin "A") (pinfunction "A_A") (pintype "passive"))
      (node (ref "C4-9") (pin "A") (pinfunction "A_A") (pintype "passive"))
      (node (ref "C5-9") (pin "A") (pinfunction "A_A") (pintype "passive"))
      (node (ref "C6-9") (pin "A") (pinfunction "A_A") (pintype "passive"))
      (node (ref "C7-9") (pin "A") (pinfunction "A_A") (pintype "passive"))
      (node (ref "C8-9") (pin "A") (pinfunction "A_A") (pintype "passive"))
      (node (ref "U1") (pin "7") (pinfunction "CB1_7") (pintype "bidirectional"))
    )
    (net (code "12") (name "/M_CB2") (class "Default")
      (node (ref "C2-10") (pin "C") (pinfunction "C_C") (pintype "passive"))
      (node (ref "C2-11") (pin "C") (pinfunction "C_C") (pintype "passive"))
      (node (ref "C2-12") (pin "C") (pinfunction "C_C") (pintype "passive"))
      (node (ref "C2-13") (pin "C") (pinfunction "C_C") (pintype "passive"))
      (node (ref "C2-14") (pin "C") (pinfunction "C_C") (pintype "passive"))
      (node (ref "C2-15") (pin "C") (pinfunction "C_C") (pintype "passive"))
      (node (ref "C2-9") (pin "C") (pinfunction "C_C") (pintype "passive"))
      (node (ref "C3-10") (pin "A") (pinfunction "A_A") (pintype "passive"))
      (node (ref "C4-10") (pin "A") (pinfunction "A_A") (pintype "passive"))
      (node (ref "C5-10") (pin "A") (pinfunction "A_A") (pintype "passive"))
      (node (ref "C6-10") (pin "A") (pinfunction "A_A") (pintype "passive"))
      (node (ref "C7-10") (pin "A") (pinfunction "A_A") (pintype "passive"))
      (node (ref "C8-10") (pin "A") (pinfunction "A_A") (pintype "passive"))
      (node (ref "U1") (pin "8") (pinfunction "CB2_8") (pintype "bidirectional"))
    )
    (net (code "13") (name "/M_CB3") (class "Default")
      (node (ref "C2-10") (pin "A") (pinfunction "A_A") (pintype "passive"))
      (node (ref "C3-10") (pin "C") (pinfunction "C_C") (pintype "passive"))
      (node (ref "C3-11") (pin "C") (pinfunction "C_C") (pintype "passive"))
      (node (ref "C3-12") (pin "C") (pinfunction "C_C") (pintype "passive"))
      (node (ref "C3-13") (pin "C") (pinfunction "C_C") (pintype "passive"))
      (node (ref "C3-14") (pin "C") (pinfunction "C_C") (pintype "passive"))
      (node (ref "C3-15") (pin "C") (pinfunction "C_C") (pintype "passive"))
      (node (ref "C3-9") (pin "C") (pinfunction "C_C") (pintype "passive"))
      (node (ref "C4-11") (pin "A") (pinfunction "A_A") (pintype "passive"))
      (node (ref "C5-11") (pin "A") (pinfunction "A_A") (pintype "passive"))
      (node (ref "C6-11") (pin "A") (pinfunction "A_A") (pintype "passive"))
      (node (ref "C7-11") (pin "A") (pinfunction "A_A") (pintype "passive"))
      (node (ref "C8-11") (pin "A") (pinfunction "A_A") (pintype "passive"))
      (node (ref "U1") (pin "9") (pinfunction "CB3_9") (pintype "bidirectional"))
    )
    (net (code "14") (name "/M_CB4") (class "Default")
      (node (ref "C2-11") (pin "A") (pinfunction "A_A") (pintype "passive"))
      (node (ref "C3-11") (pin "A") (pinfunction "A_A") (pintype "passive"))
      (node (ref "C4-10") (pin "C") (pinfunction "C_C") (pintype "passive"))
      (node (ref "C4-11") (pin "C") (pinfunction "C_C") (pintype "passive"))
      (node (ref "C4-12") (pin "C") (pinfunction "C_C") (pintype "passive"))
      (node (ref "C4-13") (pin "C") (pinfunction "C_C") (pintype "passive"))
      (node (ref "C4-14") (pin "C") (pinfunction "C_C") (pintype "passive"))
      (node (ref "C4-15") (pin "C") (pinfunction "C_C") (pintype "passive"))
      (node (ref "C4-9") (pin "C") (pinfunction "C_C") (pintype "passive"))
      (node (ref "C5-12") (pin "A") (pinfunction "A_A") (pintype "passive"))
      (node (ref "C6-12") (pin "A") (pinfunction "A_A") (pintype "passive"))
      (node (ref "C7-12") (pin "A") (pinfunction "A_A") (pintype "passive"))
      (node (ref "C8-12") (pin "A") (pinfunction "A_A") (pintype "passive"))
      (node (ref "U1") (pin "10") (pinfunction "CB4_10") (pintype "bidirectional"))
    )
    (net (code "15") (name "/M_CB5") (class "Default")
      (node (ref "C2-12") (pin "A") (pinfunction "A_A") (pintype "passive"))
      (node (ref "C3-12") (pin "A") (pinfunction "A_A") (pintype "passive"))
      (node (ref "C4-12") (pin "A") (pinfunction "A_A") (pintype "passive"))
      (node (ref "C5-10") (pin "C") (pinfunction "C_C") (pintype "passive"))
      (node (ref "C5-11") (pin "C") (pinfunction "C_C") (pintype "passive"))
      (node (ref "C5-12") (pin "C") (pinfunction "C_C") (pintype "passive"))
      (node (ref "C5-13") (pin "C") (pinfunction "C_C") (pintype "passive"))
      (node (ref "C5-14") (pin "C") (pinfunction "C_C") (pintype "passive"))
      (node (ref "C5-15") (pin "C") (pinfunction "C_C") (pintype "passive"))
      (node (ref "C5-9") (pin "C") (pinfunction "C_C") (pintype "passive"))
      (node (ref "C6-13") (pin "A") (pinfunction "A_A") (pintype "passive"))
      (node (ref "C7-13") (pin "A") (pinfunction "A_A") (pintype "passive"))
      (node (ref "C8-13") (pin "A") (pinfunction "A_A") (pintype "passive"))
      (node (ref "U1") (pin "11") (pinfunction "CB5_11") (pintype "bidirectional"))
    )
    (net (code "16") (name "/M_CB6") (class "Default")
      (node (ref "C2-13") (pin "A") (pinfunction "A_A") (pintype "passive"))
      (node (ref "C3-13") (pin "A") (pinfunction "A_A") (pintype "passive"))
      (node (ref "C4-13") (pin "A") (pinfunction "A_A") (pintype "passive"))
      (node (ref "C5-13") (pin "A") (pinfunction "A_A") (pintype "passive"))
      (node (ref "C6-10") (pin "C") (pinfunction "C_C") (pintype "passive"))
      (node (ref "C6-11") (pin "C") (pinfunction "C_C") (pintype "passive"))
      (node (ref "C6-12") (pin "C") (pinfunction "C_C") (pintype "passive"))
      (node (ref "C6-13") (pin "C") (pinfunction "C_C") (pintype "passive"))
      (node (ref "C6-14") (pin "C") (pinfunction "C_C") (pintype "passive"))
      (node (ref "C6-15") (pin "C") (pinfunction "C_C") (pintype "passive"))
      (node (ref "C6-9") (pin "C") (pinfunction "C_C") (pintype "passive"))
      (node (ref "C7-14") (pin "A") (pinfunction "A_A") (pintype "passive"))
      (node (ref "C8-14") (pin "A") (pinfunction "A_A") (pintype "passive"))
      (node (ref "U1") (pin "12") (pinfunction "CB6_12") (pintype "bidirectional"))
    )
    (net (code "17") (name "/M_CB7") (class "Default")
      (node (ref "C2-14") (pin "A") (pinfunction "A_A") (pintype "passive"))
      (node (ref "C3-14") (pin "A") (pinfunction "A_A") (pintype "passive"))
      (node (ref "C4-14") (pin "A") (pinfunction "A_A") (pintype "passive"))
      (node (ref "C5-14") (pin "A") (pinfunction "A_A") (pintype "passive"))
      (node (ref "C6-14") (pin "A") (pinfunction "A_A") (pintype "passive"))
      (node (ref "C7-10") (pin "C") (pinfunction "C_C") (pintype "passive"))
      (node (ref "C7-11") (pin "C") (pinfunction "C_C") (pintype "passive"))
      (node (ref "C7-12") (pin "C") (pinfunction "C_C") (pintype "passive"))
      (node (ref "C7-13") (pin "C") (pinfunction "C_C") (pintype "passive"))
      (node (ref "C7-14") (pin "C") (pinfunction "C_C") (pintype "passive"))
      (node (ref "C7-15") (pin "C") (pinfunction "C_C") (pintype "passive"))
      (node (ref "C7-9") (pin "C") (pinfunction "C_C") (pintype "passive"))
      (node (ref "C8-15") (pin "A") (pinfunction "A_A") (pintype "passive"))
      (node (ref "U1") (pin "13") (pinfunction "CB7_13") (pintype "bidirectional"))
    )
    (net (code "18") (name "/M_CB8") (class "Default")
      (node (ref "C2-15") (pin "A") (pinfunction "A_A") (pintype "passive"))
      (node (ref "C3-15") (pin "A") (pinfunction "A_A") (pintype "passive"))
      (node (ref "C4-15") (pin "A") (pinfunction "A_A") (pintype "passive"))
      (node (ref "C5-15") (pin "A") (pinfunction "A_A") (pintype "passive"))
      (node (ref "C6-15") (pin "A") (pinfunction "A_A") (pintype "passive"))
      (node (ref "C7-15") (pin "A") (pinfunction "A_A") (pintype "passive"))
      (node (ref "C8-10") (pin "C") (pinfunction "C_C") (pintype "passive"))
      (node (ref "C8-11") (pin "C") (pinfunction "C_C") (pintype "passive"))
      (node (ref "C8-12") (pin "C") (pinfunction "C_C") (pintype "passive"))
      (node (ref "C8-13") (pin "C") (pinfunction "C_C") (pintype "passive"))
      (node (ref "C8-14") (pin "C") (pinfunction "C_C") (pintype "passive"))
      (node (ref "C8-15") (pin "C") (pinfunction "C_C") (pintype "passive"))
      (node (ref "C8-9") (pin "C") (pinfunction "C_C") (pintype "passive"))
      (node (ref "U1") (pin "14") (pinfunction "CB8_14") (pintype "bidirectional"))
    )
    (net (code "19") (name "/M_INTB") (class "Default")
      (node (ref "U1") (pin "4") (pinfunction "INTB_4") (pintype "output"))
    )
    (net (code "20") (name "GND") (class "Default")
      (node (ref "C1") (pin "2") (pinfunction "2_2") (pintype "passive"))
      (node (ref "C2") (pin "2") (pinfunction "2_2") (pintype "passive"))
      (node (ref "C3") (pin "2") (pinfunction "2_2") (pintype "passive"))
      (node (ref "C4") (pin "2") (pinfunction "2_2") (pintype "passive"))
      (node (ref "C5") (pin "2") (pinfunction "2_2") (pintype "passive"))
      (node (ref "GND") (pin "TP") (pinfunction "TP_TP") (pintype "input"))
      (node (ref "K1") (pin "2") (pinfunction "P$2_2") (pintype "bidirectional"))
      (node (ref "R7") (pin "2") (pinfunction "2_2") (pintype "passive"))
      (node (ref "R8") (pin "1") (pinfunction "1_1") (pintype "passive"))
      (node (ref "S1") (pin "1") (pinfunction "NO_1") (pintype "bidirectional"))
      (node (ref "S2") (pin "1") (pinfunction "NO_1") (pintype "bidirectional"))
      (node (ref "U1") (pin "5") (pinfunction "GND_5") (pintype "power_in"))
      (node (ref "U1") (pin "THERMAL") (pinfunction "GND_THERMAL") (pintype "power_in"))
    )
    (net (code "21") (name "M_SCL") (class "Default")
      (node (ref "K1") (pin "4") (pinfunction "P$4_4") (pintype "bidirectional"))
      (node (ref "M_SCL") (pin "TP") (pinfunction "TP_TP") (pintype "input"))
      (node (ref "R6") (pin "1") (pinfunction "1_1") (pintype "passive"))
      (node (ref "U1") (pin "20") (pinfunction "SCL_20") (pintype "bidirectional"))
    )
    (net (code "22") (name "M_SDA") (class "Default")
      (node (ref "K1") (pin "3") (pinfunction "P$3_3") (pintype "bidirectional"))
      (node (ref "M_SDA") (pin "TP") (pinfunction "TP_TP") (pintype "input"))
      (node (ref "R4") (pin "1") (pinfunction "1_1") (pintype "passive"))
      (node (ref "U1") (pin "19") (pinfunction "SDA_19") (pintype "bidirectional"))
    )
    (net (code "23") (name "Net-(S1-COM)") (class "Default")
      (node (ref "C2") (pin "1") (pinfunction "1_1") (pintype "passive"))
      (node (ref "R1") (pin "1") (pinfunction "1_1") (pintype "passive"))
      (node (ref "R3") (pin "1") (pinfunction "1_1") (pintype "passive"))
      (node (ref "S1") (pin "2") (pinfunction "COM_2") (pintype "bidirectional"))
    )
    (net (code "24") (name "Net-(S2-COM)") (class "Default")
      (node (ref "C3") (pin "1") (pinfunction "1_1") (pintype "passive"))
      (node (ref "R2") (pin "1") (pinfunction "1_1") (pintype "passive"))
      (node (ref "R5") (pin "1") (pinfunction "1_1") (pintype "passive"))
      (node (ref "S2") (pin "2") (pinfunction "COM_2") (pintype "bidirectional"))
    )
    (net (code "25") (name "Net-(U1-R_EXT)") (class "Default")
      (node (ref "R8") (pin "2") (pinfunction "2_2") (pintype "passive"))
      (node (ref "U1") (pin "6") (pinfunction "R_EXT_6") (pintype "bidirectional"))
    )
    (net (code "26") (name "S_DOWN") (class "Default")
      (node (ref "K1") (pin "6") (pinfunction "P$6_6") (pintype "bidirectional"))
      (node (ref "R5") (pin "2") (pinfunction "2_2") (pintype "passive"))
      (node (ref "S_DOWN") (pin "TP") (pinfunction "TP_TP") (pintype "input"))
    )
    (net (code "27") (name "S_UP") (class "Default")
      (node (ref "K1") (pin "5") (pinfunction "P$5_5") (pintype "bidirectional"))
      (node (ref "R3") (pin "2") (pinfunction "2_2") (pintype "passive"))
      (node (ref "S_UP") (pin "TP") (pinfunction "TP_TP") (pintype "input"))
    )
    (net (code "28") (name "VCC") (class "Default")
      (node (ref "C1") (pin "1") (pinfunction "1_1") (pintype "passive"))
      (node (ref "C4") (pin "1") (pinfunction "1_1") (pintype "passive"))
      (node (ref "C5") (pin "1") (pinfunction "1_1") (pintype "passive"))
      (node (ref "K1") (pin "1") (pinfunction "P$1_1") (pintype "bidirectional"))
      (node (ref "R1") (pin "2") (pinfunction "2_2") (pintype "passive"))
      (node (ref "R2") (pin "2") (pinfunction "2_2") (pintype "passive"))
      (node (ref "R4") (pin "2") (pinfunction "2_2") (pintype "passive"))
      (node (ref "R6") (pin "2") (pinfunction "2_2") (pintype "passive"))
      (node (ref "U1") (pin "2") (pinfunction "VCC_2") (pintype "power_in"))
      (node (ref "U1") (pin "3") (pinfunction "SHUTDOWN_3") (pintype "input"))
      (node (ref "VCC") (pin "TP") (pinfunction "TP_TP") (pintype "input"))
    )
    (net (code "29") (name "unconnected-(U1-AUDIOIN-Pad17)") (class "Default")
      (node (ref "U1") (pin "17") (pinfunction "AUDIOIN_17") (pintype "input"))
    )
    (net (code "30") (name "unconnected-(U1-CB9-Pad15)") (class "Default")
      (node (ref "U1") (pin "15") (pinfunction "CB9_15") (pintype "bidirectional"))
    )
    (net (code "31") (name "unconnected-(U1-C_FILT-Pad16)") (class "Default")
      (node (ref "U1") (pin "16") (pinfunction "C_FILT_16") (pintype "bidirectional"))
    )
  )
)
